# Robot_arm.net
KiCad netlist of a schematic drawn in EAGLE
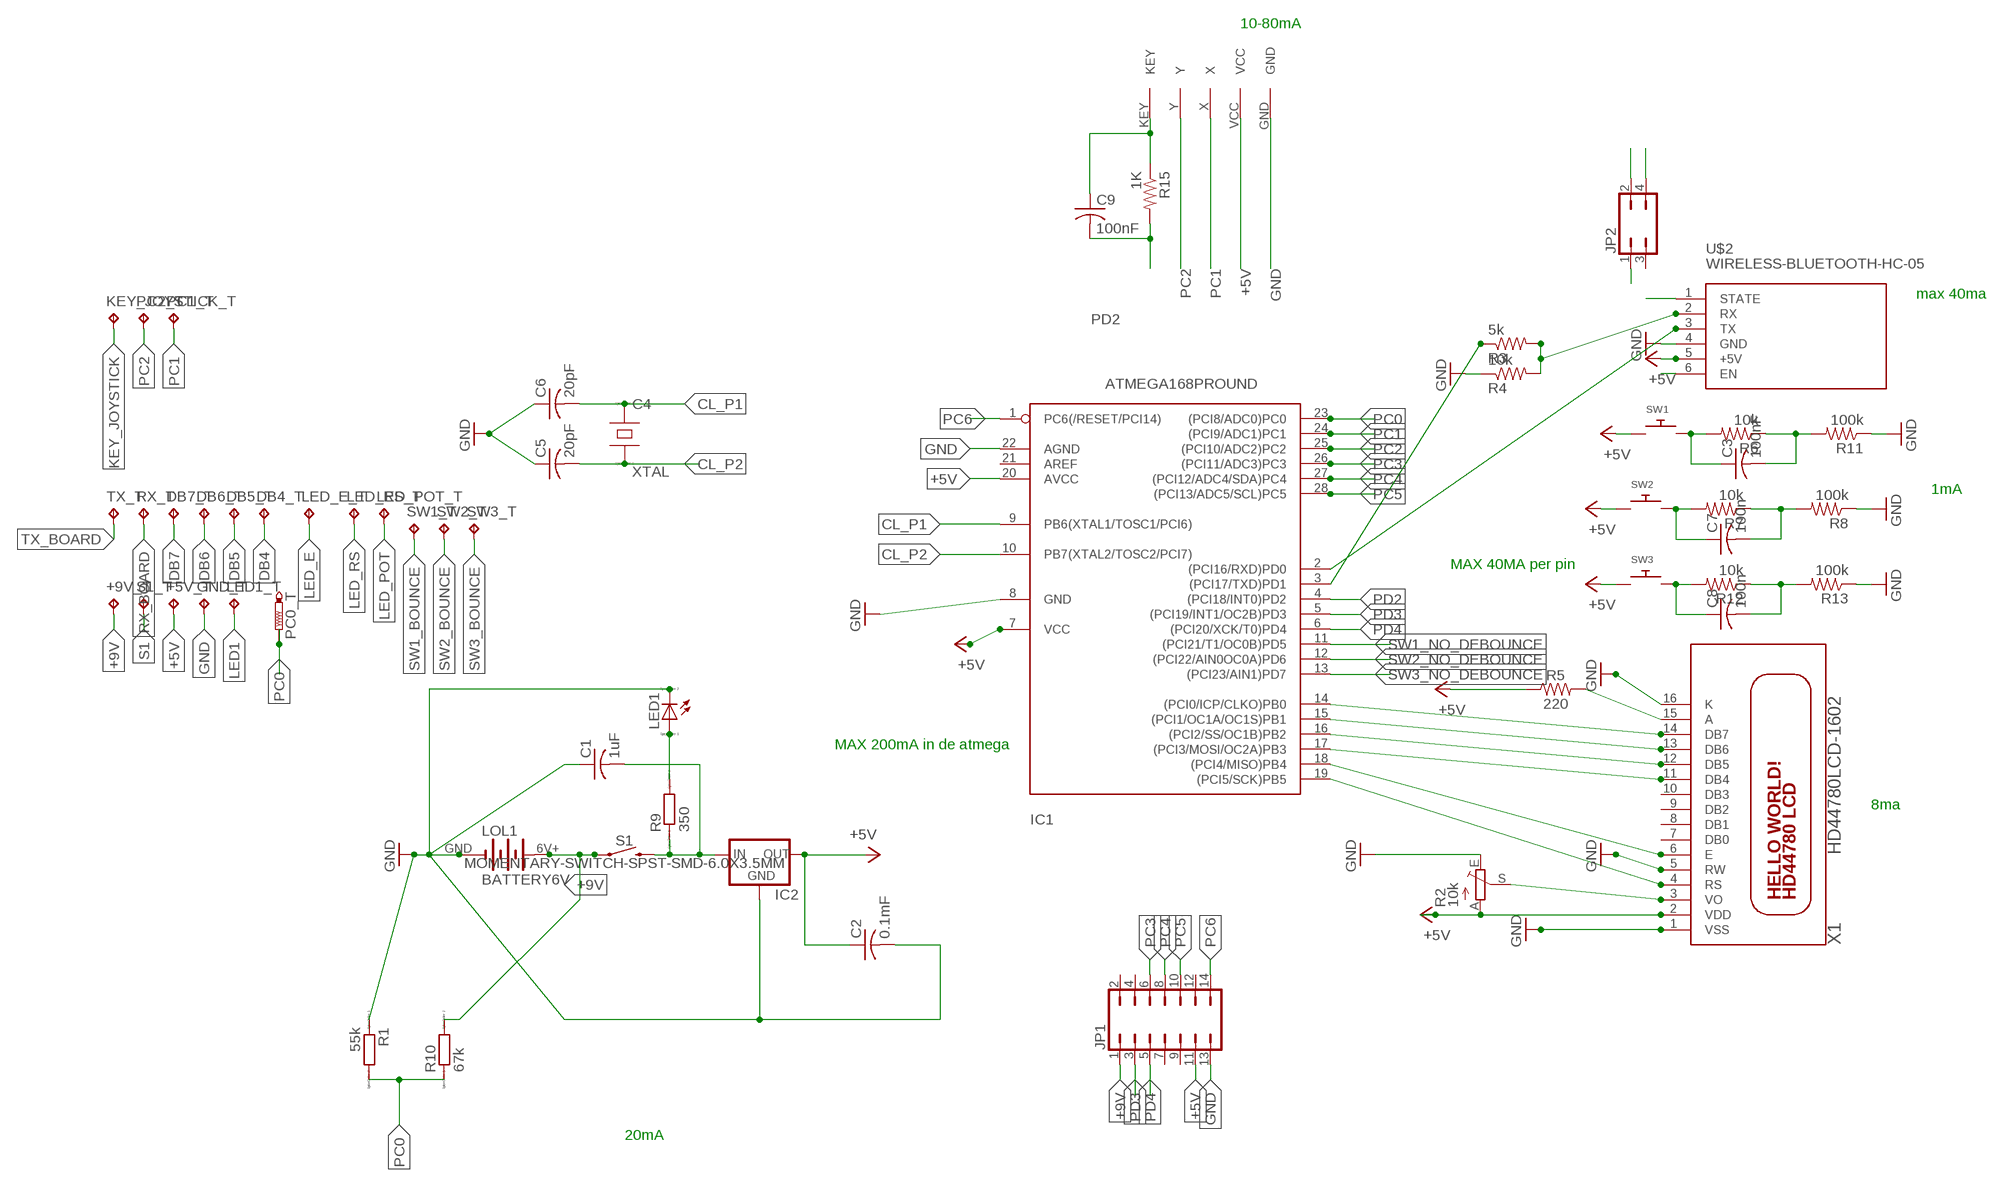
[diagram p0: schematic, sheet 1]

(export (version "E")
  (design (tool "Eeschema 10.0.6"))
  (components
    (comp (ref "+5V_T")
      (value "TPB1,27")
      (footprint "eagle-import:B1,27")
      (libsource (lib "eagle-import") (part "TPB1,27"))
    )
    (comp (ref "+9V_T")
      (value "TPB1,27")
      (footprint "eagle-import:B1,27")
      (libsource (lib "eagle-import") (part "TPB1,27"))
    )
    (comp (ref "C1")
      (value "1uF")
      (footprint "eagle-import:C025-025X050")
      (libsource (lib "eagle-import") (part "C-US025-025X050"))
    )
    (comp (ref "C2")
      (value "0.1mF")
      (footprint "eagle-import:C025-025X050")
      (libsource (lib "eagle-import") (part "C-US025-025X050"))
    )
    (comp (ref "C3")
      (value "100nF")
      (footprint "eagle-import:C025-025X050")
      (libsource (lib "eagle-import") (part "C-US025-025X050"))
    )
    (comp (ref "C4")
      (value "XTAL")
      (footprint "eagle-import:HC49UP")
      (libsource (lib "eagle-import") (part "XTAL"))
    )
    (comp (ref "C5")
      (value "20pF")
      (footprint "eagle-import:C025-025X050")
      (libsource (lib "eagle-import") (part "C-US025-025X050"))
    )
    (comp (ref "C6")
      (value "20pF")
      (footprint "eagle-import:C025-025X050")
      (libsource (lib "eagle-import") (part "C-US025-025X050"))
    )
    (comp (ref "C7")
      (value "100n")
      (footprint "eagle-import:C025-025X050")
      (libsource (lib "eagle-import") (part "C-US025-025X050"))
    )
    (comp (ref "C8")
      (value "100n")
      (footprint "eagle-import:C025-025X050")
      (libsource (lib "eagle-import") (part "C-US025-025X050"))
    )
    (comp (ref "C9")
      (value "100nF")
      (footprint "eagle-import:C025-025X050")
      (libsource (lib "eagle-import") (part "C-US025-025X050"))
    )
    (comp (ref "DB4_T")
      (value "TPB1,27")
      (footprint "eagle-import:B1,27")
      (libsource (lib "eagle-import") (part "TPB1,27"))
    )
    (comp (ref "DB5_T")
      (value "TPB1,27")
      (footprint "eagle-import:B1,27")
      (libsource (lib "eagle-import") (part "TPB1,27"))
    )
    (comp (ref "DB6_T")
      (value "TPB1,27")
      (footprint "eagle-import:B1,27")
      (libsource (lib "eagle-import") (part "TPB1,27"))
    )
    (comp (ref "DB7_T")
      (value "TPB1,27")
      (footprint "eagle-import:B1,27")
      (libsource (lib "eagle-import") (part "TPB1,27"))
    )
    (comp (ref "GND_T")
      (value "TPB1,27")
      (footprint "eagle-import:B1,27")
      (libsource (lib "eagle-import") (part "TPB1,27"))
    )
    (comp (ref "IC1")
      (value "ATMEGA168PROUND")
      (footprint "eagle-import:DIL28-3-ROUND")
      (libsource (lib "eagle-import") (part "ATMEGA168PROUND"))
    )
    (comp (ref "IC2")
      (value "MCP1700INLINE")
      (footprint "eagle-import:TO92-INLINE")
      (libsource (lib "eagle-import") (part "MCP1700INLINE"))
    )
    (comp (ref "JP1")
      (value "JP7Q")
      (footprint "eagle-import:JP7Q")
      (libsource (lib "eagle-import") (part "JP7Q"))
    )
    (comp (ref "JP2")
      (value "JP2Q")
      (footprint "eagle-import:JP2Q")
      (libsource (lib "eagle-import") (part "JP2Q"))
    )
    (comp (ref "KEY_JOYSTICK_T")
      (value "TPB1,27")
      (footprint "eagle-import:B1,27")
      (libsource (lib "eagle-import") (part "TPB1,27"))
    )
    (comp (ref "LED1")
      (value "LED_E")
      (footprint "eagle-import:LED_1206")
      (libsource (lib "eagle-import") (part "LED_E"))
    )
    (comp (ref "LED1_T")
      (value "TPB1,27")
      (footprint "eagle-import:B1,27")
      (libsource (lib "eagle-import") (part "TPB1,27"))
    )
    (comp (ref "LED_E_T")
      (value "TPB1,27")
      (footprint "eagle-import:B1,27")
      (libsource (lib "eagle-import") (part "TPB1,27"))
    )
    (comp (ref "LED_POT_T")
      (value "TPB1,27")
      (footprint "eagle-import:B1,27")
      (libsource (lib "eagle-import") (part "TPB1,27"))
    )
    (comp (ref "LED_RS_T")
      (value "TPB1,27")
      (footprint "eagle-import:B1,27")
      (libsource (lib "eagle-import") (part "TPB1,27"))
    )
    (comp (ref "LOL1")
      (value "BATTERY6V")
      (footprint "eagle-import:BATTERY6PACK")
      (libsource (lib "eagle-import") (part "BATTERY6V"))
    )
    (comp (ref "PC0_T")
      (value "PTR1B1,27")
      (footprint "eagle-import:B1,27")
      (libsource (lib "eagle-import") (part "PTR1B1,27"))
    )
    (comp (ref "PC1_T")
      (value "TPB1,27")
      (footprint "eagle-import:B1,27")
      (libsource (lib "eagle-import") (part "TPB1,27"))
    )
    (comp (ref "PC2_T")
      (value "TPB1,27")
      (footprint "eagle-import:B1,27")
      (libsource (lib "eagle-import") (part "TPB1,27"))
    )
    (comp (ref "R1")
      (value "55k")
      (footprint "eagle-import:R0805")
      (libsource (lib "eagle-import") (part "R"))
    )
    (comp (ref "R2")
      (value "10k")
      (footprint "eagle-import:B25V")
      (libsource (lib "eagle-import") (part "TRIM_EU-B25V"))
    )
    (comp (ref "R3")
      (value "5k")
      (footprint "eagle-import:0204_5")
      (libsource (lib "eagle-import") (part "R-US_0204/5"))
    )
    (comp (ref "R4")
      (value "10k")
      (footprint "eagle-import:0204_5")
      (libsource (lib "eagle-import") (part "R-US_0204/5"))
    )
    (comp (ref "R5")
      (value "220")
      (footprint "eagle-import:0603")
      (libsource (lib "eagle-import") (part "220OHM-0603-1/10W-1%"))
    )
    (comp (ref "R6")
      (value "10k")
      (footprint "eagle-import:0204_5")
      (libsource (lib "eagle-import") (part "R-US_0204/5"))
    )
    (comp (ref "R7")
      (value "10k")
      (footprint "eagle-import:0204_5")
      (libsource (lib "eagle-import") (part "R-US_0204/5"))
    )
    (comp (ref "R8")
      (value "100k")
      (footprint "eagle-import:0204_5")
      (libsource (lib "eagle-import") (part "R-US_0204/5"))
    )
    (comp (ref "R9")
      (value "350")
      (footprint "eagle-import:R0805")
      (libsource (lib "eagle-import") (part "R"))
    )
    (comp (ref "R10")
      (value "67k")
      (footprint "eagle-import:R0805")
      (libsource (lib "eagle-import") (part "R"))
    )
    (comp (ref "R11")
      (value "100k")
      (footprint "eagle-import:0204_5")
      (libsource (lib "eagle-import") (part "R-US_0204/5"))
    )
    (comp (ref "R12")
      (value "10k")
      (footprint "eagle-import:0204_5")
      (libsource (lib "eagle-import") (part "R-US_0204/5"))
    )
    (comp (ref "R13")
      (value "100k")
      (footprint "eagle-import:0204_5")
      (libsource (lib "eagle-import") (part "R-US_0204/5"))
    )
    (comp (ref "R15")
      (value "1K")
      (footprint "eagle-import:0204_5")
      (libsource (lib "eagle-import") (part "R-US_0204/5"))
    )
    (comp (ref "RX_T")
      (value "TPB1,27")
      (footprint "eagle-import:B1,27")
      (libsource (lib "eagle-import") (part "TPB1,27"))
    )
    (comp (ref "S1")
      (value "MOMENTARY-SWITCH-SPST-SMD-6.0X3.5MM")
      (footprint "eagle-import:TACTILE_SWITCH_SMD_6.0X3.5MM")
      (libsource (lib "eagle-import") (part "MOMENTARY-SWITCH-SPST-SMD-6.0X3.5MM"))
    )
    (comp (ref "S1_T")
      (value "TPB1,27")
      (footprint "eagle-import:B1,27")
      (libsource (lib "eagle-import") (part "TPB1,27"))
    )
    (comp (ref "SW1")
      (value "SWITCH_PUSHBUTTONSOFTTOUCHSMD_SJ")
      (footprint "eagle-import:PUSHBUTTON_SMD_SJ")
      (libsource (lib "eagle-import") (part "SWITCH_PUSHBUTTONSOFTTOUCHSMD_SJ"))
    )
    (comp (ref "SW1_T")
      (value "TPB1,27")
      (footprint "eagle-import:B1,27")
      (libsource (lib "eagle-import") (part "TPB1,27"))
    )
    (comp (ref "SW2")
      (value "SWITCH_PUSHBUTTONSOFTTOUCHSMD_SJ")
      (footprint "eagle-import:PUSHBUTTON_SMD_SJ")
      (libsource (lib "eagle-import") (part "SWITCH_PUSHBUTTONSOFTTOUCHSMD_SJ"))
    )
    (comp (ref "SW2_T")
      (value "TPB1,27")
      (footprint "eagle-import:B1,27")
      (libsource (lib "eagle-import") (part "TPB1,27"))
    )
    (comp (ref "SW3")
      (value "SWITCH_PUSHBUTTONSOFTTOUCHSMD_SJ")
      (footprint "eagle-import:PUSHBUTTON_SMD_SJ")
      (libsource (lib "eagle-import") (part "SWITCH_PUSHBUTTONSOFTTOUCHSMD_SJ"))
    )
    (comp (ref "SW3_T")
      (value "TPB1,27")
      (footprint "eagle-import:B1,27")
      (libsource (lib "eagle-import") (part "TPB1,27"))
    )
    (comp (ref "TX_T")
      (value "TPB1,27")
      (footprint "eagle-import:B1,27")
      (libsource (lib "eagle-import") (part "TPB1,27"))
    )
    (comp (ref "U$1")
      (value "JOYSTICK")
      (footprint "eagle-import:JOYSTICK")
      (libsource (lib "eagle-import") (part "JOYSTICK"))
    )
    (comp (ref "U$2")
      (value "WIRELESS-BLUETOOTH-HC-05")
      (footprint "eagle-import:WIRELESS-BLUETOOTH-HC-05")
      (libsource (lib "eagle-import") (part "WIRELESS-BLUETOOTH-HC-05"))
    )
    (comp (ref "X1")
      (value "HD44780LCD-1602")
      (footprint "eagle-import:LCD1602")
      (libsource (lib "eagle-import") (part "HD44780LCD-1602"))
    )
  )
  (nets
    (net (code "1") (name "+5V") (class "Default")
      (node (ref "+5V_T") (pin "TP") (pinfunction "TP_TP") (pintype "input"))
      (node (ref "C2") (pin "1") (pinfunction "1_1") (pintype "passive"))
      (node (ref "IC1") (pin "20") (pinfunction "AVCC_20") (pintype "bidirectional"))
      (node (ref "IC1") (pin "7") (pinfunction "VCC_7") (pintype "bidirectional"))
      (node (ref "IC2") (pin "3") (pinfunction "OUT_3") (pintype "passive"))
      (node (ref "JP1") (pin "11") (pinfunction "11_11") (pintype "passive"))
      (node (ref "R2") (pin "A") (pinfunction "A_A") (pintype "passive"))
      (node (ref "R5") (pin "1") (pinfunction "1_1") (pintype "passive"))
      (node (ref "SW1") (pin "P$1") (pinfunction "P$1_P$1") (pintype "passive"))
      (node (ref "SW2") (pin "P$1") (pinfunction "P$1_P$1") (pintype "passive"))
      (node (ref "SW3") (pin "P$1") (pinfunction "P$1_P$1") (pintype "passive"))
      (node (ref "U$1") (pin "VCC") (pinfunction "VCC_VCC") (pintype "bidirectional"))
      (node (ref "U$2") (pin "5") (pinfunction "+5V_5") (pintype "power_in"))
      (node (ref "X1") (pin "2") (pinfunction "VDD_2") (pintype "power_in"))
    )
    (net (code "2") (name "+9V") (class "Default")
      (node (ref "+9V_T") (pin "TP") (pinfunction "TP_TP") (pintype "input"))
      (node (ref "JP1") (pin "1") (pinfunction "1_1") (pintype "passive"))
      (node (ref "LOL1") (pin "6V+") (pinfunction "6V_6V+") (pintype "passive"))
      (node (ref "R10") (pin "2") (pinfunction "2_2") (pintype "passive"))
      (node (ref "S1") (pin "1") (pinfunction "1_1") (pintype "passive"))
    )
    (net (code "3") (name "/EN") (class "Default")
      (node (ref "JP2") (pin "4") (pinfunction "4_4") (pintype "passive"))
      (node (ref "U$2") (pin "6") (pinfunction "EN_6") (pintype "bidirectional"))
    )
    (net (code "4") (name "/STATE") (class "Default")
      (node (ref "JP2") (pin "2") (pinfunction "2_2") (pintype "passive"))
      (node (ref "U$2") (pin "1") (pinfunction "STATE_1") (pintype "bidirectional"))
    )
    (net (code "5") (name "CL_P1") (class "Default")
      (node (ref "C4") (pin "1") (pinfunction "A_1") (pintype "passive"))
      (node (ref "C6") (pin "2") (pinfunction "2_2") (pintype "passive"))
      (node (ref "IC1") (pin "9") (pinfunction "PB6(XTAL1/TOSC1/PCI6)_9") (pintype "bidirectional"))
    )
    (net (code "6") (name "CL_P2") (class "Default")
      (node (ref "C4") (pin "2") (pinfunction "B_2") (pintype "passive"))
      (node (ref "C5") (pin "2") (pinfunction "2_2") (pintype "passive"))
      (node (ref "IC1") (pin "10") (pinfunction "PB7(XTAL2/TOSC2/PCI7)_10") (pintype "bidirectional"))
    )
    (net (code "7") (name "DB4") (class "Default")
      (node (ref "DB4_T") (pin "TP") (pinfunction "TP_TP") (pintype "input"))
      (node (ref "IC1") (pin "17") (pinfunction "(PCI3/MOSI/OC2A)PB3_17") (pintype "bidirectional"))
      (node (ref "X1") (pin "11") (pinfunction "DB4_11") (pintype "bidirectional"))
    )
    (net (code "8") (name "DB5") (class "Default")
      (node (ref "DB5_T") (pin "TP") (pinfunction "TP_TP") (pintype "input"))
      (node (ref "IC1") (pin "16") (pinfunction "(PCI2/SS/OC1B)PB2_16") (pintype "bidirectional"))
      (node (ref "X1") (pin "12") (pinfunction "DB5_12") (pintype "bidirectional"))
    )
    (net (code "9") (name "DB6") (class "Default")
      (node (ref "DB6_T") (pin "TP") (pinfunction "TP_TP") (pintype "input"))
      (node (ref "IC1") (pin "15") (pinfunction "(PCI1/OC1A/OC1S)PB1_15") (pintype "bidirectional"))
      (node (ref "X1") (pin "13") (pinfunction "DB6_13") (pintype "bidirectional"))
    )
    (net (code "10") (name "DB7") (class "Default")
      (node (ref "DB7_T") (pin "TP") (pinfunction "TP_TP") (pintype "input"))
      (node (ref "IC1") (pin "14") (pinfunction "(PCI0/ICP/CLKO)PB0_14") (pintype "bidirectional"))
      (node (ref "X1") (pin "14") (pinfunction "DB7_14") (pintype "bidirectional"))
    )
    (net (code "11") (name "GND") (class "Default")
      (node (ref "C1") (pin "1") (pinfunction "1_1") (pintype "passive"))
      (node (ref "C2") (pin "2") (pinfunction "2_2") (pintype "passive"))
      (node (ref "C5") (pin "1") (pinfunction "1_1") (pintype "passive"))
      (node (ref "C6") (pin "1") (pinfunction "1_1") (pintype "passive"))
      (node (ref "GND_T") (pin "TP") (pinfunction "TP_TP") (pintype "input"))
      (node (ref "IC1") (pin "22") (pinfunction "AGND_22") (pintype "bidirectional"))
      (node (ref "IC1") (pin "8") (pinfunction "GND_8") (pintype "bidirectional"))
      (node (ref "IC2") (pin "1") (pinfunction "GND_1") (pintype "input"))
      (node (ref "JP1") (pin "13") (pinfunction "13_13") (pintype "passive"))
      (node (ref "JP2") (pin "1") (pinfunction "1_1") (pintype "passive"))
      (node (ref "LED1") (pin "C") (pinfunction "C_C") (pintype "passive"))
      (node (ref "LOL1") (pin "GND") (pinfunction "GND_GND") (pintype "passive"))
      (node (ref "R1") (pin "1") (pinfunction "1_1") (pintype "passive"))
      (node (ref "R11") (pin "1") (pinfunction "1_1") (pintype "passive"))
      (node (ref "R13") (pin "1") (pinfunction "1_1") (pintype "passive"))
      (node (ref "R2") (pin "E") (pinfunction "E_E") (pintype "passive"))
      (node (ref "R4") (pin "1") (pinfunction "1_1") (pintype "passive"))
      (node (ref "R8") (pin "1") (pinfunction "1_1") (pintype "passive"))
      (node (ref "U$1") (pin "GND") (pinfunction "GND_GND") (pintype "bidirectional"))
      (node (ref "U$2") (pin "4") (pinfunction "GND_4") (pintype "power_in"))
      (node (ref "X1") (pin "1") (pinfunction "VSS_1") (pintype "power_in"))
      (node (ref "X1") (pin "16") (pinfunction "K_16") (pintype "input"))
      (node (ref "X1") (pin "5") (pinfunction "RW_5") (pintype "input"))
    )
    (net (code "12") (name "KEY_JOYSTICK") (class "Default")
      (node (ref "C9") (pin "1") (pinfunction "1_1") (pintype "passive"))
      (node (ref "KEY_JOYSTICK_T") (pin "TP") (pinfunction "TP_TP") (pintype "input"))
      (node (ref "R15") (pin "1") (pinfunction "1_1") (pintype "passive"))
      (node (ref "U$1") (pin "KEY") (pinfunction "KEY_KEY") (pintype "bidirectional"))
    )
    (net (code "13") (name "LED1") (class "Default")
      (node (ref "LED1") (pin "A") (pinfunction "A_A") (pintype "passive"))
      (node (ref "LED1_T") (pin "TP") (pinfunction "TP_TP") (pintype "input"))
      (node (ref "R9") (pin "2") (pinfunction "2_2") (pintype "passive"))
    )
    (net (code "14") (name "LED_E") (class "Default")
      (node (ref "IC1") (pin "18") (pinfunction "(PCI4/MISO)PB4_18") (pintype "bidirectional"))
      (node (ref "LED_E_T") (pin "TP") (pinfunction "TP_TP") (pintype "input"))
      (node (ref "X1") (pin "6") (pinfunction "E_6") (pintype "input"))
    )
    (net (code "15") (name "LED_POT") (class "Default")
      (node (ref "LED_POT_T") (pin "TP") (pinfunction "TP_TP") (pintype "input"))
      (node (ref "R2") (pin "S") (pinfunction "S_S") (pintype "passive"))
      (node (ref "X1") (pin "3") (pinfunction "VO_3") (pintype "input"))
    )
    (net (code "16") (name "LED_RS") (class "Default")
      (node (ref "IC1") (pin "19") (pinfunction "(PCI5/SCK)PB5_19") (pintype "bidirectional"))
      (node (ref "LED_RS_T") (pin "TP") (pinfunction "TP_TP") (pintype "input"))
      (node (ref "X1") (pin "4") (pinfunction "RS_4") (pintype "input"))
    )
    (net (code "17") (name "Net-(U$2-RX)") (class "Default")
      (node (ref "R3") (pin "2") (pinfunction "2_2") (pintype "passive"))
      (node (ref "R4") (pin "2") (pinfunction "2_2") (pintype "passive"))
      (node (ref "U$2") (pin "2") (pinfunction "RX_2") (pintype "bidirectional"))
    )
    (net (code "18") (name "Net-(X1-A)") (class "Default")
      (node (ref "R5") (pin "2") (pinfunction "2_2") (pintype "passive"))
      (node (ref "X1") (pin "15") (pinfunction "A_15") (pintype "input"))
    )
    (net (code "19") (name "PC0") (class "Default")
      (node (ref "IC1") (pin "23") (pinfunction "(PCI8/ADC0)PC0_23") (pintype "bidirectional"))
      (node (ref "PC0_T") (pin "TP") (pinfunction "TP_TP") (pintype "input"))
      (node (ref "R1") (pin "2") (pinfunction "2_2") (pintype "passive"))
      (node (ref "R10") (pin "1") (pinfunction "1_1") (pintype "passive"))
    )
    (net (code "20") (name "PC1") (class "Default")
      (node (ref "IC1") (pin "24") (pinfunction "(PCI9/ADC1)PC1_24") (pintype "bidirectional"))
      (node (ref "PC1_T") (pin "TP") (pinfunction "TP_TP") (pintype "input"))
      (node (ref "U$1") (pin "X") (pinfunction "X_X") (pintype "bidirectional"))
    )
    (net (code "21") (name "PC2") (class "Default")
      (node (ref "IC1") (pin "25") (pinfunction "(PCI10/ADC2)PC2_25") (pintype "bidirectional"))
      (node (ref "PC2_T") (pin "TP") (pinfunction "TP_TP") (pintype "input"))
      (node (ref "U$1") (pin "Y") (pinfunction "Y_Y") (pintype "bidirectional"))
    )
    (net (code "22") (name "PC3") (class "Default")
      (node (ref "IC1") (pin "26") (pinfunction "(PCI11/ADC3)PC3_26") (pintype "bidirectional"))
      (node (ref "JP1") (pin "6") (pinfunction "6_6") (pintype "passive"))
    )
    (net (code "23") (name "PC4") (class "Default")
      (node (ref "IC1") (pin "27") (pinfunction "(PCI12/ADC4/SDA)PC4_27") (pintype "bidirectional"))
      (node (ref "JP1") (pin "8") (pinfunction "8_8") (pintype "passive"))
    )
    (net (code "24") (name "PC5") (class "Default")
      (node (ref "IC1") (pin "28") (pinfunction "(PCI13/ADC5/SCL)PC5_28") (pintype "bidirectional"))
      (node (ref "JP1") (pin "10") (pinfunction "10_10") (pintype "passive"))
    )
    (net (code "25") (name "PC6") (class "Default")
      (node (ref "IC1") (pin "1") (pinfunction "PC6(/RESET/PCI14)_1") (pintype "bidirectional"))
      (node (ref "JP1") (pin "14") (pinfunction "14_14") (pintype "passive"))
    )
    (net (code "26") (name "PD2") (class "Default")
      (node (ref "C9") (pin "2") (pinfunction "2_2") (pintype "passive"))
      (node (ref "IC1") (pin "4") (pinfunction "(PCI18/INT0)PD2_4") (pintype "bidirectional"))
      (node (ref "R15") (pin "2") (pinfunction "2_2") (pintype "passive"))
    )
    (net (code "27") (name "PD3") (class "Default")
      (node (ref "IC1") (pin "5") (pinfunction "(PCI19/INT1/OC2B)PD3_5") (pintype "bidirectional"))
      (node (ref "JP1") (pin "3") (pinfunction "3_3") (pintype "passive"))
    )
    (net (code "28") (name "PD4") (class "Default")
      (node (ref "IC1") (pin "6") (pinfunction "(PCI20/XCK/T0)PD4_6") (pintype "bidirectional"))
      (node (ref "JP1") (pin "5") (pinfunction "5_5") (pintype "passive"))
    )
    (net (code "29") (name "RX_BOARD") (class "Default")
      (node (ref "IC1") (pin "2") (pinfunction "(PCI16/RXD)PD0_2") (pintype "bidirectional"))
      (node (ref "RX_T") (pin "TP") (pinfunction "TP_TP") (pintype "input"))
      (node (ref "U$2") (pin "3") (pinfunction "TX_3") (pintype "bidirectional"))
    )
    (net (code "30") (name "S1") (class "Default")
      (node (ref "C1") (pin "2") (pinfunction "2_2") (pintype "passive"))
      (node (ref "IC2") (pin "2") (pinfunction "IN_2") (pintype "input"))
      (node (ref "R9") (pin "1") (pinfunction "1_1") (pintype "passive"))
      (node (ref "S1") (pin "2") (pinfunction "2_2") (pintype "passive"))
      (node (ref "S1_T") (pin "TP") (pinfunction "TP_TP") (pintype "input"))
    )
    (net (code "31") (name "SW1_BOUNCE") (class "Default")
      (node (ref "C3") (pin "1") (pinfunction "1_1") (pintype "passive"))
      (node (ref "R6") (pin "2") (pinfunction "2_2") (pintype "passive"))
      (node (ref "SW1") (pin "P$2") (pinfunction "P$2_P$2") (pintype "passive"))
      (node (ref "SW1_T") (pin "TP") (pinfunction "TP_TP") (pintype "input"))
    )
    (net (code "32") (name "SW1_NO_DEBOUNCE") (class "Default")
      (node (ref "C3") (pin "2") (pinfunction "2_2") (pintype "passive"))
      (node (ref "IC1") (pin "11") (pinfunction "(PCI21/T1/OC0B)PD5_11") (pintype "bidirectional"))
      (node (ref "R11") (pin "2") (pinfunction "2_2") (pintype "passive"))
      (node (ref "R6") (pin "1") (pinfunction "1_1") (pintype "passive"))
    )
    (net (code "33") (name "SW2_BOUNCE") (class "Default")
      (node (ref "C7") (pin "1") (pinfunction "1_1") (pintype "passive"))
      (node (ref "R7") (pin "2") (pinfunction "2_2") (pintype "passive"))
      (node (ref "SW2") (pin "P$2") (pinfunction "P$2_P$2") (pintype "passive"))
      (node (ref "SW2_T") (pin "TP") (pinfunction "TP_TP") (pintype "input"))
    )
    (net (code "34") (name "SW2_NO_DEBOUNCE") (class "Default")
      (node (ref "C7") (pin "2") (pinfunction "2_2") (pintype "passive"))
      (node (ref "IC1") (pin "12") (pinfunction "(PCI22/AIN0OC0A)PD6_12") (pintype "bidirectional"))
      (node (ref "R7") (pin "1") (pinfunction "1_1") (pintype "passive"))
      (node (ref "R8") (pin "2") (pinfunction "2_2") (pintype "passive"))
    )
    (net (code "35") (name "SW3_BOUNCE") (class "Default")
      (node (ref "C8") (pin "1") (pinfunction "1_1") (pintype "passive"))
      (node (ref "R12") (pin "2") (pinfunction "2_2") (pintype "passive"))
      (node (ref "SW3") (pin "P$2") (pinfunction "P$2_P$2") (pintype "passive"))
      (node (ref "SW3_T") (pin "TP") (pinfunction "TP_TP") (pintype "input"))
    )
    (net (code "36") (name "SW3_NO_DEBOUNCE") (class "Default")
      (node (ref "C8") (pin "2") (pinfunction "2_2") (pintype "passive"))
      (node (ref "IC1") (pin "13") (pinfunction "(PCI23/AIN1)PD7_13") (pintype "bidirectional"))
      (node (ref "R12") (pin "1") (pinfunction "1_1") (pintype "passive"))
      (node (ref "R13") (pin "2") (pinfunction "2_2") (pintype "passive"))
    )
    (net (code "37") (name "TX_BOARD") (class "Default")
      (node (ref "IC1") (pin "3") (pinfunction "(PCI17/TXD)PD1_3") (pintype "bidirectional"))
      (node (ref "R3") (pin "1") (pinfunction "1_1") (pintype "passive"))
      (node (ref "TX_T") (pin "TP") (pinfunction "TP_TP") (pintype "input"))
    )
    (net (code "38") (name "unconnected-(IC1-AREF-Pad21)") (class "Default")
      (node (ref "IC1") (pin "21") (pinfunction "AREF_21") (pintype "bidirectional"))
    )
    (net (code "39") (name "unconnected-(JP1-Pad2)") (class "Default")
      (node (ref "JP1") (pin "2") (pinfunction "2_2") (pintype "passive"))
    )
    (net (code "40") (name "unconnected-(JP1-Pad4)") (class "Default")
      (node (ref "JP1") (pin "4") (pinfunction "4_4") (pintype "passive"))
    )
    (net (code "41") (name "unconnected-(JP1-Pad7)") (class "Default")
      (node (ref "JP1") (pin "7") (pinfunction "7_7") (pintype "passive"))
    )
    (net (code "42") (name "unconnected-(JP1-Pad9)") (class "Default")
      (node (ref "JP1") (pin "9") (pinfunction "9_9") (pintype "passive"))
    )
    (net (code "43") (name "unconnected-(JP1-Pad12)") (class "Default")
      (node (ref "JP1") (pin "12") (pinfunction "12_12") (pintype "passive"))
    )
    (net (code "44") (name "unconnected-(JP2-Pad3)") (class "Default")
      (node (ref "JP2") (pin "3") (pinfunction "3_3") (pintype "passive"))
    )
    (net (code "45") (name "unconnected-(X1-DB0-Pad7)") (class "Default")
      (node (ref "X1") (pin "7") (pinfunction "DB0_7") (pintype "bidirectional"))
    )
    (net (code "46") (name "unconnected-(X1-DB1-Pad8)") (class "Default")
      (node (ref "X1") (pin "8") (pinfunction "DB1_8") (pintype "bidirectional"))
    )
    (net (code "47") (name "unconnected-(X1-DB2-Pad9)") (class "Default")
      (node (ref "X1") (pin "9") (pinfunction "DB2_9") (pintype "bidirectional"))
    )
    (net (code "48") (name "unconnected-(X1-DB3-Pad10)") (class "Default")
      (node (ref "X1") (pin "10") (pinfunction "DB3_10") (pintype "bidirectional"))
    )
  )
)
